# Adafruit_CAN_Pal_Breakout.net
KiCad netlist of a schematic drawn in EAGLE
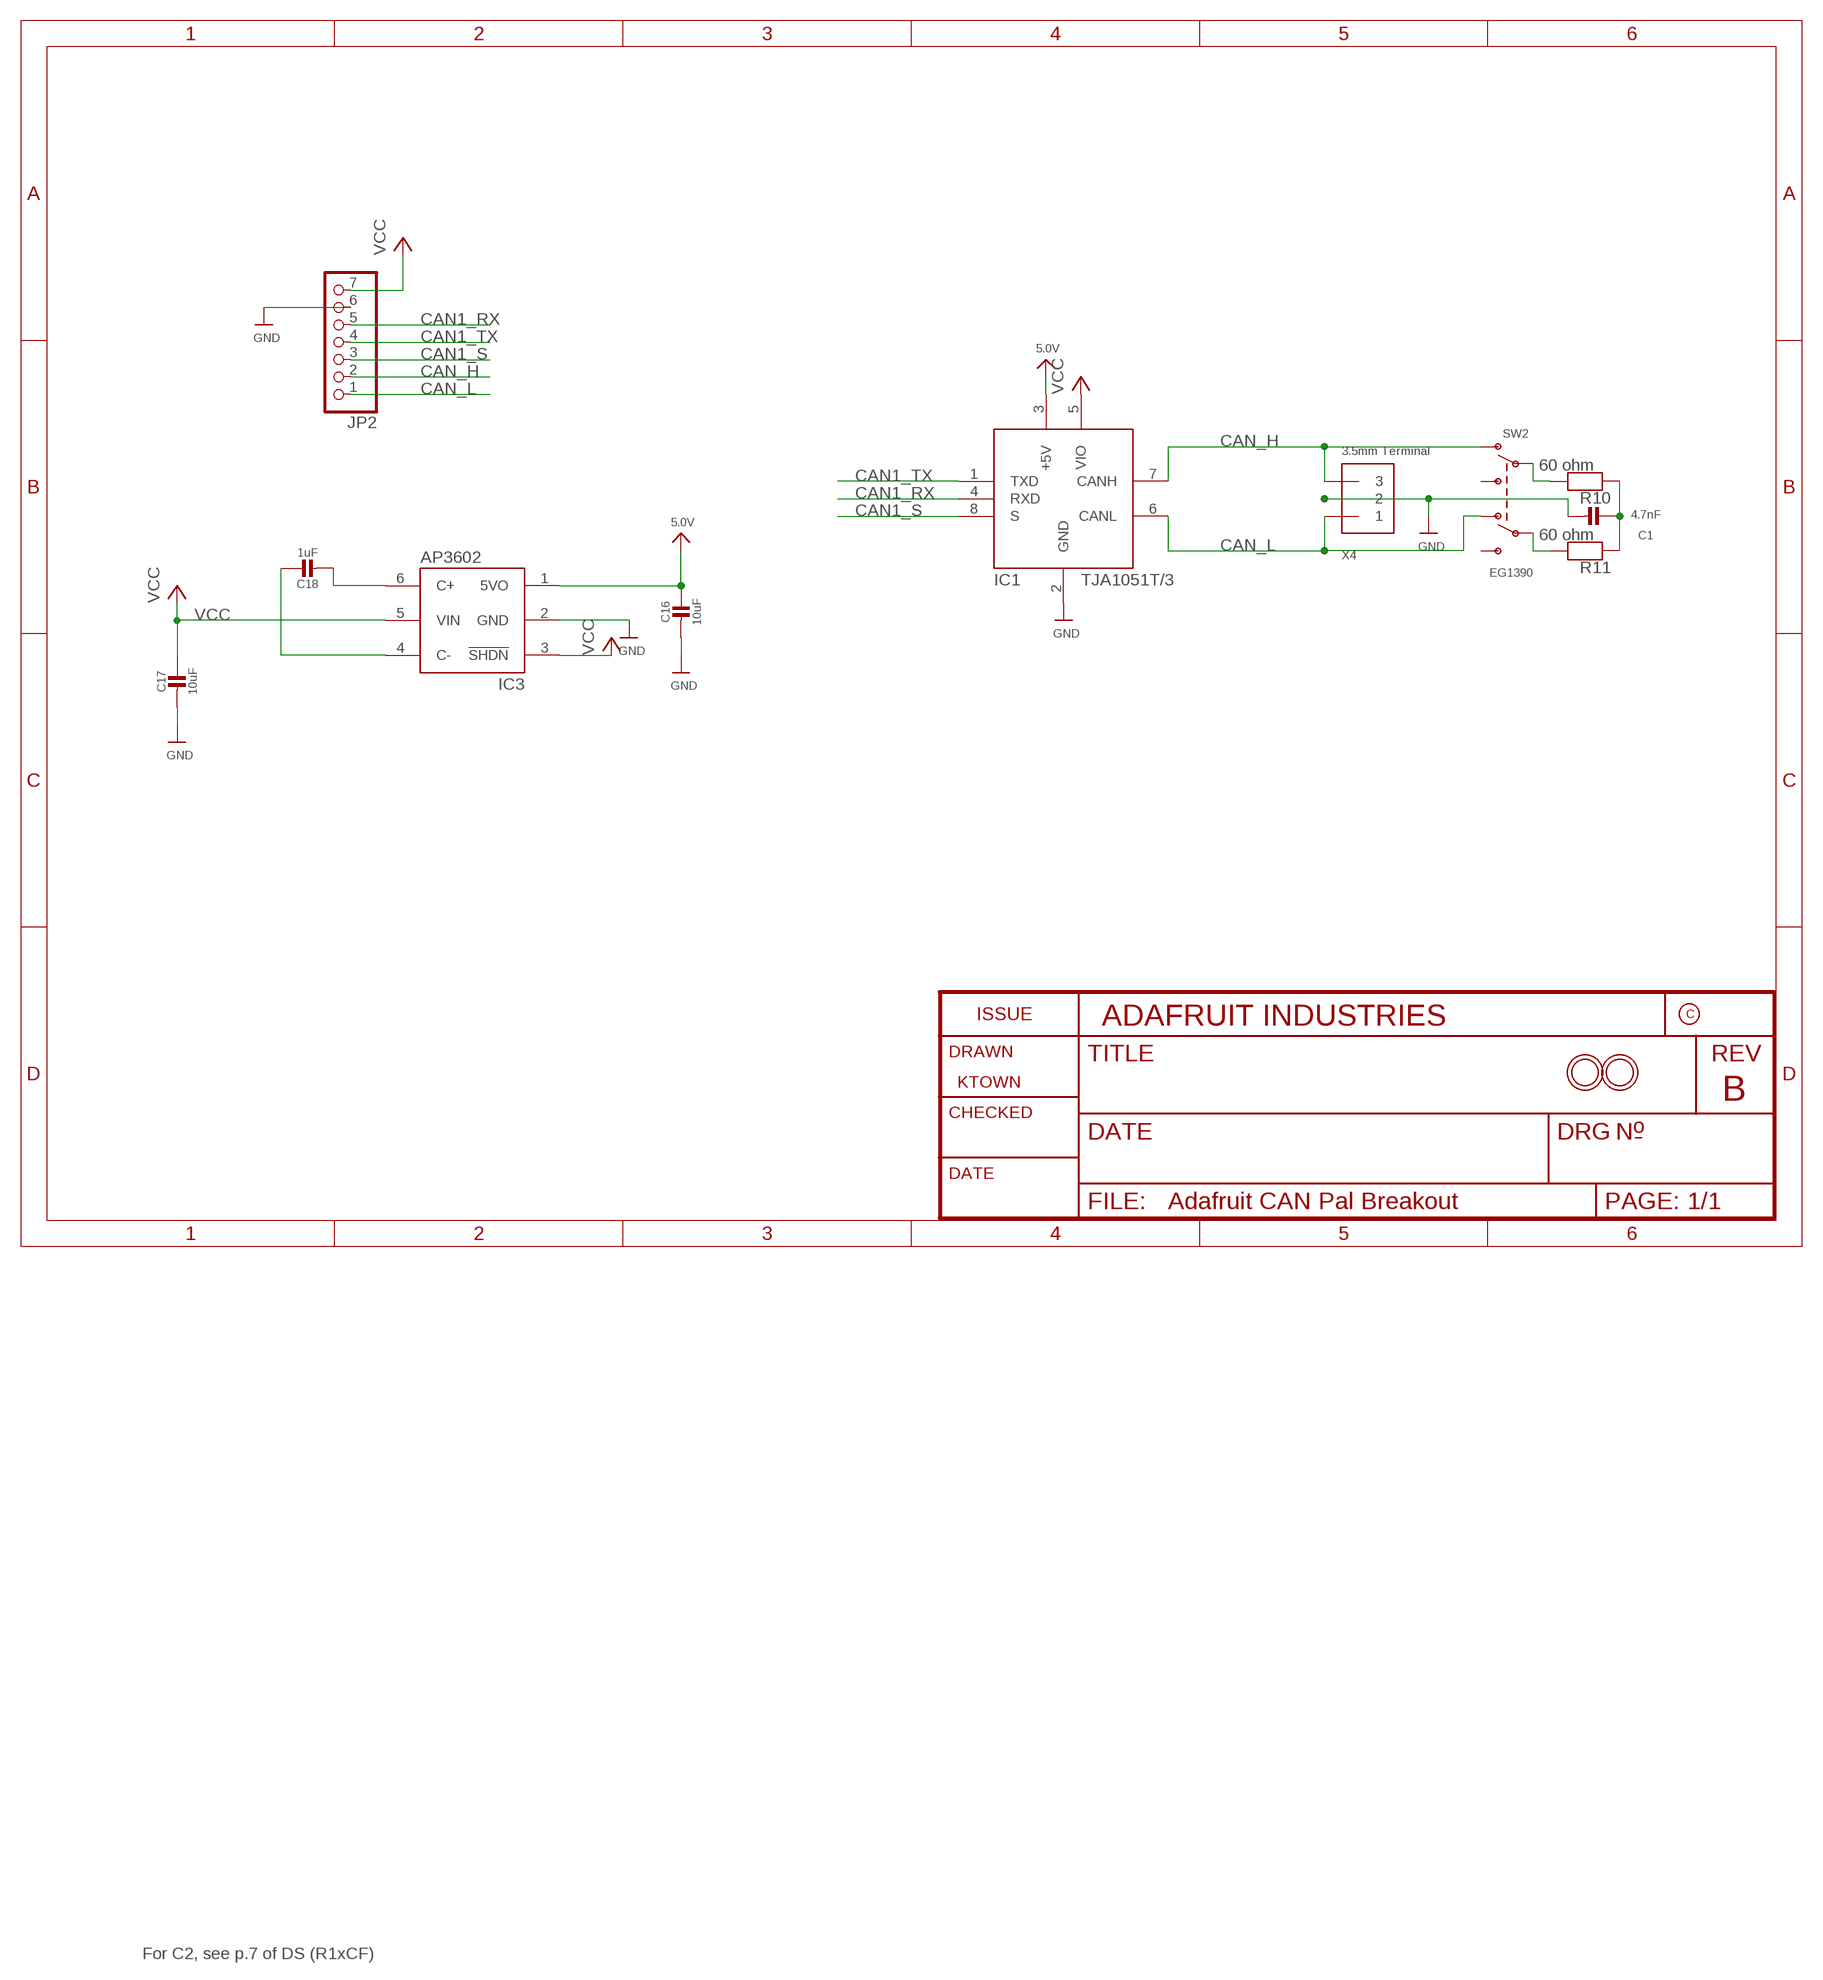
[diagram p0: schematic, sheet 1]

(export (version "E")
  (design (tool "Eeschema 10.0.6"))
  (components
    (comp (ref "C1")
      (value "4.7nF")
      (footprint "eagle-import:0603-NO")
      (libsource (lib "eagle-import") (part "CAP_CERAMIC0603_NO"))
    )
    (comp (ref "C16")
      (value "10uF")
      (footprint "eagle-import:0805-NO")
      (libsource (lib "eagle-import") (part "CAP_CERAMIC0805-NOOUTLINE"))
    )
    (comp (ref "C17")
      (value "10uF")
      (footprint "eagle-import:0805-NO")
      (libsource (lib "eagle-import") (part "CAP_CERAMIC0805-NOOUTLINE"))
    )
    (comp (ref "C18")
      (value "1uF")
      (footprint "eagle-import:0805_10MGAP")
      (libsource (lib "eagle-import") (part "CAP_CERAMIC0805_10MGAP"))
    )
    (comp (ref "IC1")
      (value "TJA1051T/3")
      (footprint "eagle-import:SOIC8_150MIL")
      (libsource (lib "eagle-import") (part "CAN_TRANSCIEVER_TCAN1051V"))
    )
    (comp (ref "IC3")
      (value "AP3602")
      (footprint "eagle-import:SOT23-6")
      (libsource (lib "eagle-import") (part "AP3602"))
    )
    (comp (ref "JP2")
      (value "HEADER-1X770MIL")
      (footprint "eagle-import:1X07_ROUND_70")
      (libsource (lib "eagle-import") (part "HEADER-1X770MIL"))
    )
    (comp (ref "R10")
      (value "60 ohm")
      (footprint "eagle-import:0603-NO")
      (libsource (lib "eagle-import") (part "RESISTOR_0603_NOOUT"))
    )
    (comp (ref "R11")
      (value "60 ohm")
      (footprint "eagle-import:0603-NO")
      (libsource (lib "eagle-import") (part "RESISTOR_0603_NOOUT"))
    )
    (comp (ref "SW2")
      (value "EG1390")
      (footprint "eagle-import:EG1390")
      (libsource (lib "eagle-import") (part "SWITCH_DPDTEG1390"))
    )
    (comp (ref "U$2")
      (value "MOUNTINGHOLE2.5")
      (footprint "eagle-import:MOUNTINGHOLE_2.5_PLATED")
      (libsource (lib "eagle-import") (part "MOUNTINGHOLE2.5"))
    )
    (comp (ref "U$3")
      (value "MOUNTINGHOLE2.5")
      (footprint "eagle-import:MOUNTINGHOLE_2.5_PLATED")
      (libsource (lib "eagle-import") (part "MOUNTINGHOLE2.5"))
    )
    (comp (ref "X4")
      (value "3.5mm Terminal")
      (footprint "eagle-import:TERMBLOCK_1X3-3.5MM")
      (libsource (lib "eagle-import") (part "TERMBLOCK_1X3"))
    )
  )
  (nets
    (net (code "1") (name "/CAN1_RX") (class "Default")
      (node (ref "IC1") (pin "4") (pinfunction "RXD_4") (pintype "output"))
      (node (ref "JP2") (pin "5") (pinfunction "5_5") (pintype "passive"))
    )
    (net (code "2") (name "/CAN1_S") (class "Default")
      (node (ref "IC1") (pin "8") (pinfunction "S_8") (pintype "input"))
      (node (ref "JP2") (pin "3") (pinfunction "3_3") (pintype "passive"))
    )
    (net (code "3") (name "/CAN1_TX") (class "Default")
      (node (ref "IC1") (pin "1") (pinfunction "TXD_1") (pintype "input"))
      (node (ref "JP2") (pin "4") (pinfunction "4_4") (pintype "passive"))
    )
    (net (code "4") (name "/CAN_H") (class "Default")
      (node (ref "IC1") (pin "7") (pinfunction "CANH_7") (pintype "bidirectional"))
      (node (ref "JP2") (pin "2") (pinfunction "2_2") (pintype "passive"))
      (node (ref "SW2") (pin "O1") (pinfunction "O1_O1") (pintype "passive"))
      (node (ref "X4") (pin "3") (pinfunction "3_3") (pintype "passive"))
    )
    (net (code "5") (name "/CAN_L") (class "Default")
      (node (ref "IC1") (pin "6") (pinfunction "CANL_6") (pintype "bidirectional"))
      (node (ref "JP2") (pin "1") (pinfunction "1_1") (pintype "passive"))
      (node (ref "SW2") (pin "O2") (pinfunction "O2_O2") (pintype "passive"))
      (node (ref "X4") (pin "1") (pinfunction "1_1") (pintype "passive"))
    )
    (net (code "6") (name "5.0V") (class "Default")
      (node (ref "C16") (pin "1") (pinfunction "1_1") (pintype "passive"))
      (node (ref "IC1") (pin "3") (pinfunction "+5V_3") (pintype "power_in"))
      (node (ref "IC3") (pin "1") (pinfunction "5VO_1") (pintype "power_in"))
    )
    (net (code "7") (name "GND") (class "Default")
      (node (ref "C1") (pin "2") (pinfunction "2_2") (pintype "passive"))
      (node (ref "C16") (pin "2") (pinfunction "2_2") (pintype "passive"))
      (node (ref "C17") (pin "2") (pinfunction "2_2") (pintype "passive"))
      (node (ref "IC1") (pin "2") (pinfunction "GND_2") (pintype "power_in"))
      (node (ref "IC3") (pin "2") (pinfunction "GND_2") (pintype "power_in"))
      (node (ref "JP2") (pin "6") (pinfunction "6_6") (pintype "passive"))
      (node (ref "X4") (pin "2") (pinfunction "2_2") (pintype "passive"))
    )
    (net (code "8") (name "Net-(C1-Pad1)") (class "Default")
      (node (ref "C1") (pin "1") (pinfunction "1_1") (pintype "passive"))
      (node (ref "R10") (pin "1") (pinfunction "1_1") (pintype "passive"))
      (node (ref "R11") (pin "1") (pinfunction "1_1") (pintype "passive"))
    )
    (net (code "9") (name "Net-(IC3-C+)") (class "Default")
      (node (ref "C18") (pin "2") (pinfunction "2_2") (pintype "passive"))
      (node (ref "IC3") (pin "6") (pinfunction "C+_6") (pintype "bidirectional"))
    )
    (net (code "10") (name "Net-(IC3-C-)") (class "Default")
      (node (ref "C18") (pin "1") (pinfunction "1_1") (pintype "passive"))
      (node (ref "IC3") (pin "4") (pinfunction "C-_4") (pintype "bidirectional"))
    )
    (net (code "11") (name "Net-(R10-Pad2)") (class "Default")
      (node (ref "R10") (pin "2") (pinfunction "2_2") (pintype "passive"))
      (node (ref "SW2") (pin "P1") (pinfunction "P1_P1") (pintype "passive"))
    )
    (net (code "12") (name "Net-(R11-Pad2)") (class "Default")
      (node (ref "R11") (pin "2") (pinfunction "2_2") (pintype "passive"))
      (node (ref "SW2") (pin "P2") (pinfunction "P2_P2") (pintype "passive"))
    )
    (net (code "13") (name "VCC") (class "Default")
      (node (ref "C17") (pin "1") (pinfunction "1_1") (pintype "passive"))
      (node (ref "IC1") (pin "5") (pinfunction "VIO_5") (pintype "power_in"))
      (node (ref "IC3") (pin "3") (pinfunction "~{SHDN}_3") (pintype "input"))
      (node (ref "IC3") (pin "5") (pinfunction "VIN_5") (pintype "power_in"))
      (node (ref "JP2") (pin "7") (pinfunction "7_7") (pintype "passive"))
    )
    (net (code "14") (name "unconnected-(SW2-PadS1)") (class "Default")
      (node (ref "SW2") (pin "S1") (pinfunction "S1_S1") (pintype "passive"))
    )
    (net (code "15") (name "unconnected-(SW2-PadS2)") (class "Default")
      (node (ref "SW2") (pin "S2") (pinfunction "S2_S2") (pintype "passive"))
    )
  )
)
